# Odbiornik_3.net
KiCad netlist of a schematic drawn in EAGLE
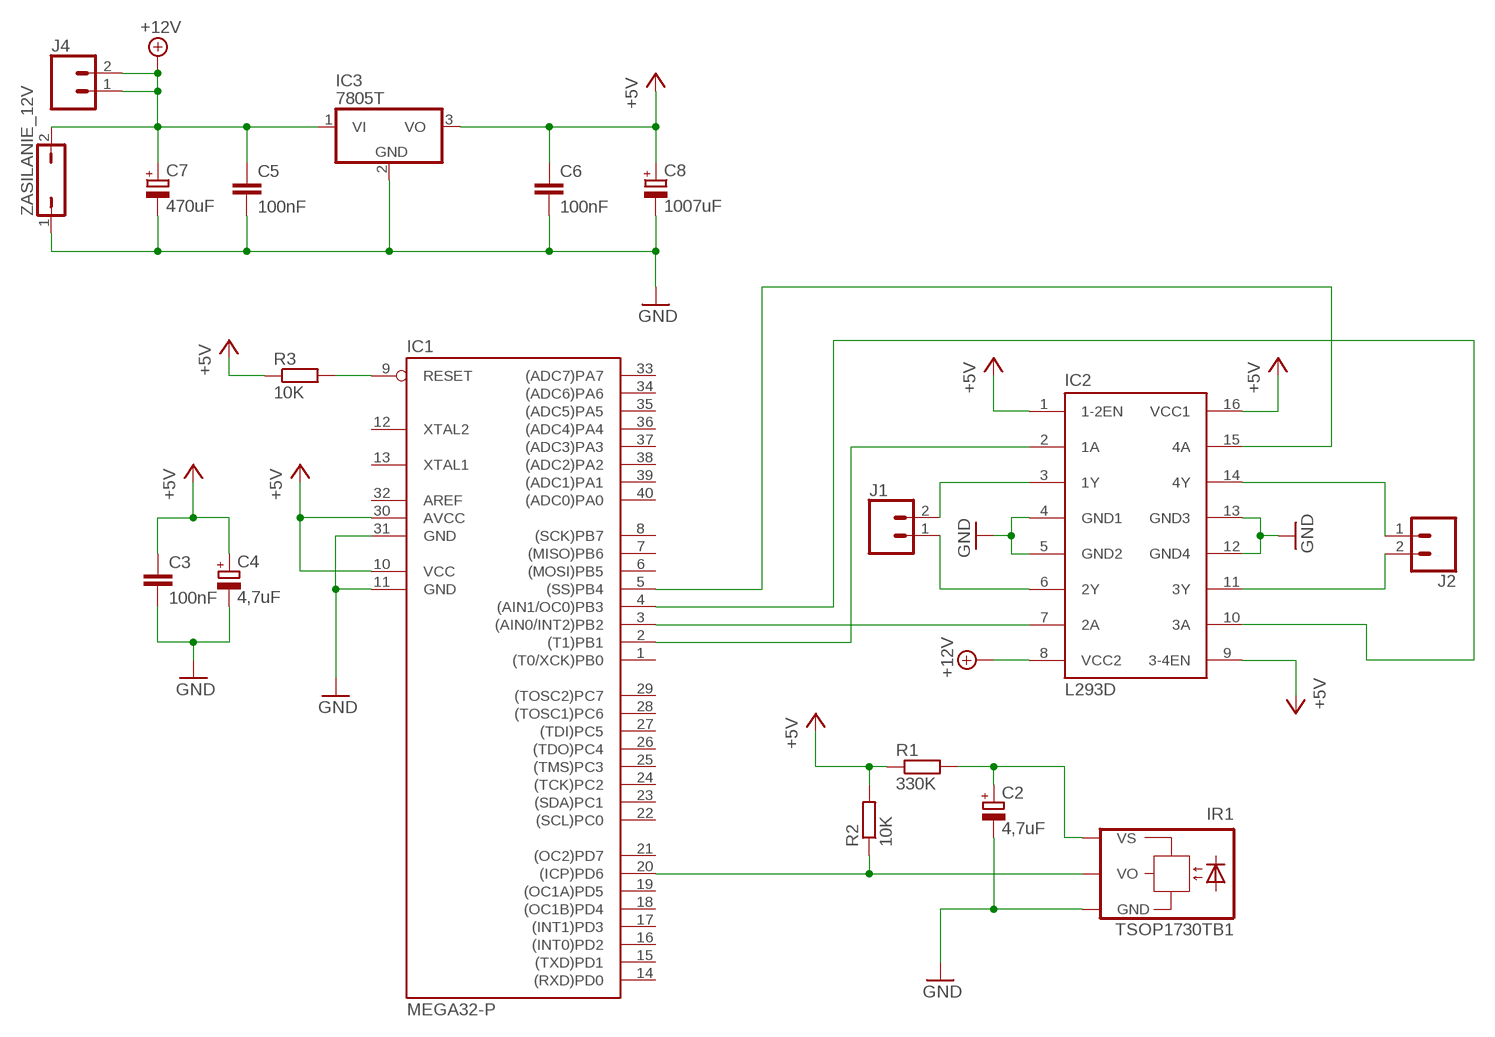
[diagram p0: schematic, sheet 1]

(export (version "E")
  (design (tool "Eeschema 10.0.6"))
  (components
    (comp (ref "C2")
      (value "4,7uF")
      (footprint "eagle-import:E2-4")
      (libsource (lib "eagle-import") (part "CPOL-EUE2-4"))
    )
    (comp (ref "C3")
      (value "100nF")
      (footprint "eagle-import:C025-024X044")
      (libsource (lib "eagle-import") (part "C-EU025-024X044"))
    )
    (comp (ref "C4")
      (value "4,7uF")
      (footprint "eagle-import:E2-4")
      (libsource (lib "eagle-import") (part "CPOL-EUE2-4"))
    )
    (comp (ref "C5")
      (value "100nF")
      (footprint "eagle-import:C025-024X044")
      (libsource (lib "eagle-import") (part "C-EU025-024X044"))
    )
    (comp (ref "C6")
      (value "100nF")
      (footprint "eagle-import:C025-024X044")
      (libsource (lib "eagle-import") (part "C-EU025-024X044"))
    )
    (comp (ref "C7")
      (value "470uF")
      (footprint "eagle-import:E2-4")
      (libsource (lib "eagle-import") (part "CPOL-EUE2-4"))
    )
    (comp (ref "C8")
      (value "1007uF")
      (footprint "eagle-import:E2-4")
      (libsource (lib "eagle-import") (part "CPOL-EUE2-4"))
    )
    (comp (ref "IC1")
      (value "MEGA32-P")
      (footprint "eagle-import:DIL40")
      (fields (field (name "MPN") "ATMEGA32-16PU"))
      (libsource (lib "eagle-import") (part "MEGA32-P"))
    )
    (comp (ref "IC2")
      (value "L293D")
      (footprint "eagle-import:DIL16")
      (libsource (lib "eagle-import") (part "L293D"))
    )
    (comp (ref "IC3")
      (value "7805T")
      (footprint "eagle-import:TO220H")
      (libsource (lib "eagle-import") (part "78T05"))
    )
    (comp (ref "IR1")
      (value "TSOP1730TB1")
      (footprint "eagle-import:TSOP17_TB1")
      (libsource (lib "eagle-import") (part "TSOP17TB130"))
    )
    (comp (ref "J1")
      (value "CONN_02")
      (footprint "eagle-import:1X02")
      (libsource (lib "eagle-import") (part "CONN_02"))
    )
    (comp (ref "J2")
      (value "CONN_02")
      (footprint "eagle-import:1X02")
      (libsource (lib "eagle-import") (part "CONN_02"))
    )
    (comp (ref "J4")
      (value "CONN_02")
      (footprint "eagle-import:1X02")
      (libsource (lib "eagle-import") (part "CONN_02"))
    )
    (comp (ref "R1")
      (value "330K")
      (footprint "eagle-import:0204_5")
      (libsource (lib "eagle-import") (part "R-EU_0204/5"))
    )
    (comp (ref "R2")
      (value "10K")
      (footprint "eagle-import:0204_5")
      (libsource (lib "eagle-import") (part "R-EU_0204/5"))
    )
    (comp (ref "R3")
      (value "10K")
      (footprint "eagle-import:0204_5")
      (libsource (lib "eagle-import") (part "R-EU_0204/5"))
    )
    (comp (ref "ZASILANIE_12V")
      (value "JP1Q")
      (footprint "eagle-import:JP1")
      (libsource (lib "eagle-import") (part "JP1Q"))
    )
  )
  (nets
    (net (code "1") (name "+5V") (class "Default")
      (node (ref "C3") (pin "1") (pinfunction "1_1") (pintype "passive"))
      (node (ref "C4") (pin "+") (pinfunction "+_+") (pintype "passive"))
      (node (ref "C6") (pin "1") (pinfunction "1_1") (pintype "passive"))
      (node (ref "C8") (pin "+") (pinfunction "+_+") (pintype "passive"))
      (node (ref "IC1") (pin "10") (pinfunction "VCC_10") (pintype "power_in"))
      (node (ref "IC1") (pin "30") (pinfunction "AVCC_30") (pintype "power_in"))
      (node (ref "IC2") (pin "1") (pinfunction "1-2EN_1") (pintype "input"))
      (node (ref "IC2") (pin "16") (pinfunction "VCC1_16") (pintype "power_in"))
      (node (ref "IC2") (pin "9") (pinfunction "3-4EN_9") (pintype "input"))
      (node (ref "IC3") (pin "3") (pinfunction "VO_3") (pintype "passive"))
      (node (ref "R1") (pin "1") (pinfunction "1_1") (pintype "passive"))
      (node (ref "R2") (pin "2") (pinfunction "2_2") (pintype "passive"))
      (node (ref "R3") (pin "1") (pinfunction "1_1") (pintype "passive"))
    )
    (net (code "2") (name "+12V") (class "Default")
      (node (ref "C5") (pin "1") (pinfunction "1_1") (pintype "passive"))
      (node (ref "C7") (pin "+") (pinfunction "+_+") (pintype "passive"))
      (node (ref "IC2") (pin "8") (pinfunction "VCC2_8") (pintype "power_in"))
      (node (ref "IC3") (pin "1") (pinfunction "VI_1") (pintype "input"))
      (node (ref "J4") (pin "1") (pinfunction "1_1") (pintype "passive"))
      (node (ref "J4") (pin "2") (pinfunction "2_2") (pintype "passive"))
      (node (ref "ZASILANIE_12V") (pin "2") (pinfunction "2_2") (pintype "passive"))
    )
    (net (code "3") (name "GND") (class "Default")
      (node (ref "C2") (pin "-") (pinfunction "-_-") (pintype "passive"))
      (node (ref "C3") (pin "2") (pinfunction "2_2") (pintype "passive"))
      (node (ref "C4") (pin "-") (pinfunction "-_-") (pintype "passive"))
      (node (ref "C5") (pin "2") (pinfunction "2_2") (pintype "passive"))
      (node (ref "C6") (pin "2") (pinfunction "2_2") (pintype "passive"))
      (node (ref "C7") (pin "-") (pinfunction "-_-") (pintype "passive"))
      (node (ref "C8") (pin "-") (pinfunction "-_-") (pintype "passive"))
      (node (ref "IC1") (pin "11") (pinfunction "GND_11") (pintype "power_in"))
      (node (ref "IC1") (pin "31") (pinfunction "GND_31") (pintype "power_in"))
      (node (ref "IC2") (pin "12") (pinfunction "GND4_12") (pintype "power_in"))
      (node (ref "IC2") (pin "13") (pinfunction "GND3_13") (pintype "power_in"))
      (node (ref "IC2") (pin "4") (pinfunction "GND1_4") (pintype "power_in"))
      (node (ref "IC2") (pin "5") (pinfunction "GND2_5") (pintype "power_in"))
      (node (ref "IC3") (pin "2") (pinfunction "GND_2") (pintype "passive"))
      (node (ref "IR1") (pin "GND") (pinfunction "GND_GND") (pintype "power_in"))
      (node (ref "ZASILANIE_12V") (pin "1") (pinfunction "1_1") (pintype "passive"))
    )
    (net (code "4") (name "Net-(C2-Pad+)") (class "Default")
      (node (ref "C2") (pin "+") (pinfunction "+_+") (pintype "passive"))
      (node (ref "IR1") (pin "VS") (pinfunction "VS_VS") (pintype "power_in"))
      (node (ref "R1") (pin "2") (pinfunction "2_2") (pintype "passive"))
    )
    (net (code "5") (name "Net-(IC1-(AIN0{slash}INT2)PB2)") (class "Default")
      (node (ref "IC1") (pin "3") (pinfunction "(AIN0/INT2)PB2_3") (pintype "bidirectional"))
      (node (ref "IC2") (pin "7") (pinfunction "2A_7") (pintype "input"))
    )
    (net (code "6") (name "Net-(IC1-(AIN1{slash}OC0)PB3)") (class "Default")
      (node (ref "IC1") (pin "4") (pinfunction "(AIN1/OC0)PB3_4") (pintype "bidirectional"))
      (node (ref "IC2") (pin "10") (pinfunction "3A_10") (pintype "input"))
    )
    (net (code "7") (name "Net-(IC1-(ICP)PD6)") (class "Default")
      (node (ref "IC1") (pin "20") (pinfunction "(ICP)PD6_20") (pintype "bidirectional"))
      (node (ref "IR1") (pin "VO") (pinfunction "VO_VO") (pintype "open_collector"))
      (node (ref "R2") (pin "1") (pinfunction "1_1") (pintype "passive"))
    )
    (net (code "8") (name "Net-(IC1-(SS)PB4)") (class "Default")
      (node (ref "IC1") (pin "5") (pinfunction "(SS)PB4_5") (pintype "bidirectional"))
      (node (ref "IC2") (pin "15") (pinfunction "4A_15") (pintype "input"))
    )
    (net (code "9") (name "Net-(IC1-(T1)PB1)") (class "Default")
      (node (ref "IC1") (pin "2") (pinfunction "(T1)PB1_2") (pintype "bidirectional"))
      (node (ref "IC2") (pin "2") (pinfunction "1A_2") (pintype "input"))
    )
    (net (code "10") (name "Net-(IC1-RESET)") (class "Default")
      (node (ref "IC1") (pin "9") (pinfunction "RESET_9") (pintype "input"))
      (node (ref "R3") (pin "2") (pinfunction "2_2") (pintype "passive"))
    )
    (net (code "11") (name "Net-(IC2-1Y)") (class "Default")
      (node (ref "IC2") (pin "3") (pinfunction "1Y_3") (pintype "output"))
      (node (ref "J1") (pin "2") (pinfunction "2_2") (pintype "passive"))
    )
    (net (code "12") (name "Net-(IC2-2Y)") (class "Default")
      (node (ref "IC2") (pin "6") (pinfunction "2Y_6") (pintype "output"))
      (node (ref "J1") (pin "1") (pinfunction "1_1") (pintype "passive"))
    )
    (net (code "13") (name "Net-(IC2-3Y)") (class "Default")
      (node (ref "IC2") (pin "11") (pinfunction "3Y_11") (pintype "output"))
      (node (ref "J2") (pin "2") (pinfunction "2_2") (pintype "passive"))
    )
    (net (code "14") (name "Net-(IC2-4Y)") (class "Default")
      (node (ref "IC2") (pin "14") (pinfunction "4Y_14") (pintype "output"))
      (node (ref "J2") (pin "1") (pinfunction "1_1") (pintype "passive"))
    )
    (net (code "15") (name "unconnected-(IC1-(ADC0)PA0-Pad40)") (class "Default")
      (node (ref "IC1") (pin "40") (pinfunction "(ADC0)PA0_40") (pintype "bidirectional"))
    )
    (net (code "16") (name "unconnected-(IC1-(ADC1)PA1-Pad39)") (class "Default")
      (node (ref "IC1") (pin "39") (pinfunction "(ADC1)PA1_39") (pintype "bidirectional"))
    )
    (net (code "17") (name "unconnected-(IC1-(ADC2)PA2-Pad38)") (class "Default")
      (node (ref "IC1") (pin "38") (pinfunction "(ADC2)PA2_38") (pintype "bidirectional"))
    )
    (net (code "18") (name "unconnected-(IC1-(ADC3)PA3-Pad37)") (class "Default")
      (node (ref "IC1") (pin "37") (pinfunction "(ADC3)PA3_37") (pintype "bidirectional"))
    )
    (net (code "19") (name "unconnected-(IC1-(ADC4)PA4-Pad36)") (class "Default")
      (node (ref "IC1") (pin "36") (pinfunction "(ADC4)PA4_36") (pintype "bidirectional"))
    )
    (net (code "20") (name "unconnected-(IC1-(ADC5)PA5-Pad35)") (class "Default")
      (node (ref "IC1") (pin "35") (pinfunction "(ADC5)PA5_35") (pintype "bidirectional"))
    )
    (net (code "21") (name "unconnected-(IC1-(ADC6)PA6-Pad34)") (class "Default")
      (node (ref "IC1") (pin "34") (pinfunction "(ADC6)PA6_34") (pintype "bidirectional"))
    )
    (net (code "22") (name "unconnected-(IC1-(ADC7)PA7-Pad33)") (class "Default")
      (node (ref "IC1") (pin "33") (pinfunction "(ADC7)PA7_33") (pintype "bidirectional"))
    )
    (net (code "23") (name "unconnected-(IC1-(INT0)PD2-Pad16)") (class "Default")
      (node (ref "IC1") (pin "16") (pinfunction "(INT0)PD2_16") (pintype "bidirectional"))
    )
    (net (code "24") (name "unconnected-(IC1-(INT1)PD3-Pad17)") (class "Default")
      (node (ref "IC1") (pin "17") (pinfunction "(INT1)PD3_17") (pintype "bidirectional"))
    )
    (net (code "25") (name "unconnected-(IC1-(MISO)PB6-Pad7)") (class "Default")
      (node (ref "IC1") (pin "7") (pinfunction "(MISO)PB6_7") (pintype "bidirectional"))
    )
    (net (code "26") (name "unconnected-(IC1-(MOSI)PB5-Pad6)") (class "Default")
      (node (ref "IC1") (pin "6") (pinfunction "(MOSI)PB5_6") (pintype "bidirectional"))
    )
    (net (code "27") (name "unconnected-(IC1-(OC1A)PD5-Pad19)") (class "Default")
      (node (ref "IC1") (pin "19") (pinfunction "(OC1A)PD5_19") (pintype "bidirectional"))
    )
    (net (code "28") (name "unconnected-(IC1-(OC1B)PD4-Pad18)") (class "Default")
      (node (ref "IC1") (pin "18") (pinfunction "(OC1B)PD4_18") (pintype "bidirectional"))
    )
    (net (code "29") (name "unconnected-(IC1-(OC2)PD7-Pad21)") (class "Default")
      (node (ref "IC1") (pin "21") (pinfunction "(OC2)PD7_21") (pintype "bidirectional"))
    )
    (net (code "30") (name "unconnected-(IC1-(RXD)PD0-Pad14)") (class "Default")
      (node (ref "IC1") (pin "14") (pinfunction "(RXD)PD0_14") (pintype "bidirectional"))
    )
    (net (code "31") (name "unconnected-(IC1-(SCK)PB7-Pad8)") (class "Default")
      (node (ref "IC1") (pin "8") (pinfunction "(SCK)PB7_8") (pintype "bidirectional"))
    )
    (net (code "32") (name "unconnected-(IC1-(SCL)PC0-Pad22)") (class "Default")
      (node (ref "IC1") (pin "22") (pinfunction "(SCL)PC0_22") (pintype "bidirectional"))
    )
    (net (code "33") (name "unconnected-(IC1-(SDA)PC1-Pad23)") (class "Default")
      (node (ref "IC1") (pin "23") (pinfunction "(SDA)PC1_23") (pintype "bidirectional"))
    )
    (net (code "34") (name "unconnected-(IC1-(T0{slash}XCK)PB0-Pad1)") (class "Default")
      (node (ref "IC1") (pin "1") (pinfunction "(T0/XCK)PB0_1") (pintype "bidirectional"))
    )
    (net (code "35") (name "unconnected-(IC1-(TCK)PC2-Pad24)") (class "Default")
      (node (ref "IC1") (pin "24") (pinfunction "(TCK)PC2_24") (pintype "bidirectional"))
    )
    (net (code "36") (name "unconnected-(IC1-(TDI)PC5-Pad27)") (class "Default")
      (node (ref "IC1") (pin "27") (pinfunction "(TDI)PC5_27") (pintype "bidirectional"))
    )
    (net (code "37") (name "unconnected-(IC1-(TDO)PC4-Pad26)") (class "Default")
      (node (ref "IC1") (pin "26") (pinfunction "(TDO)PC4_26") (pintype "bidirectional"))
    )
    (net (code "38") (name "unconnected-(IC1-(TMS)PC3-Pad25)") (class "Default")
      (node (ref "IC1") (pin "25") (pinfunction "(TMS)PC3_25") (pintype "bidirectional"))
    )
    (net (code "39") (name "unconnected-(IC1-(TOSC1)PC6-Pad28)") (class "Default")
      (node (ref "IC1") (pin "28") (pinfunction "(TOSC1)PC6_28") (pintype "bidirectional"))
    )
    (net (code "40") (name "unconnected-(IC1-(TOSC2)PC7-Pad29)") (class "Default")
      (node (ref "IC1") (pin "29") (pinfunction "(TOSC2)PC7_29") (pintype "bidirectional"))
    )
    (net (code "41") (name "unconnected-(IC1-(TXD)PD1-Pad15)") (class "Default")
      (node (ref "IC1") (pin "15") (pinfunction "(TXD)PD1_15") (pintype "bidirectional"))
    )
    (net (code "42") (name "unconnected-(IC1-AREF-Pad32)") (class "Default")
      (node (ref "IC1") (pin "32") (pinfunction "AREF_32") (pintype "passive"))
    )
    (net (code "43") (name "unconnected-(IC1-XTAL1-Pad13)") (class "Default")
      (node (ref "IC1") (pin "13") (pinfunction "XTAL1_13") (pintype "bidirectional"))
    )
    (net (code "44") (name "unconnected-(IC1-XTAL2-Pad12)") (class "Default")
      (node (ref "IC1") (pin "12") (pinfunction "XTAL2_12") (pintype "bidirectional"))
    )
  )
)
